# Bypass_FPGA_1V2.net
KiCad netlist of a schematic drawn in Altium Designer
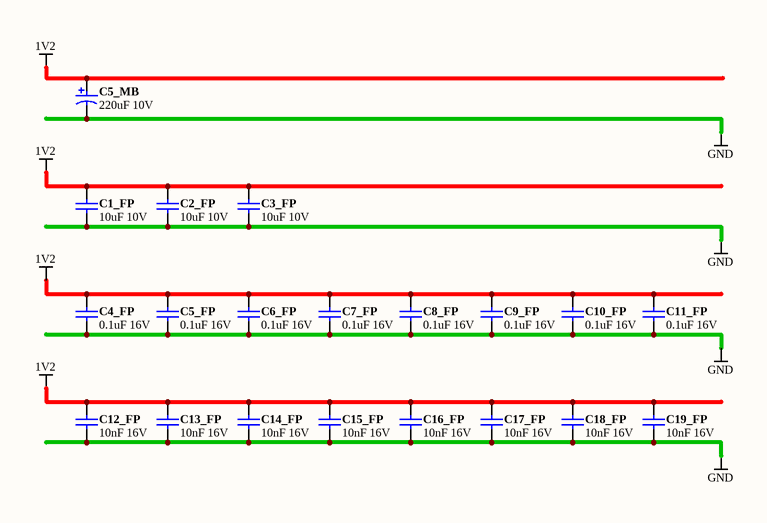
[diagram p0: Bypass_FPGA_1V2.SCHDOC]

(export (version "E")
  (design (tool "Eeschema 10.0.6"))
  (components
    (comp (ref "C1_FP")
      (value "10uF 10V")
      (footprint "CAPC2012-STAR")
      (description "Capacitor, Ceramic, 10uF 10% 10V 0805 (2012) X5R")
      (fields (field (name "TOLERANCE") "10 %"))
      (libsource (lib "AltiumDesignLibrary") (part "CAP-NP"))
    )
    (comp (ref "C2_FP")
      (value "10uF 10V")
      (footprint "CAPC2012-STAR")
      (description "Capacitor, Ceramic, 10uF 10% 10V 0805 (2012) X5R")
      (fields (field (name "TOLERANCE") "10 %"))
      (libsource (lib "AltiumDesignLibrary") (part "CAP-NP"))
    )
    (comp (ref "C3_FP")
      (value "10uF 10V")
      (footprint "CAPC2012-STAR")
      (description "Capacitor, Ceramic, 10uF 10% 10V 0805 (2012) X5R")
      (fields (field (name "TOLERANCE") "10 %"))
      (libsource (lib "AltiumDesignLibrary") (part "CAP-NP"))
    )
    (comp (ref "C4_FP")
      (value "0.1uF 16V")
      (footprint "CAPC1005-STAR")
      (description "Capacitor, Ceramic, 0.1uF 10% 16V 0402 (1005) X7R")
      (fields (field (name "TOLERANCE") "10 %"))
      (libsource (lib "AltiumDesignLibrary") (part "CAP-NP"))
    )
    (comp (ref "C5_FP")
      (value "0.1uF 16V")
      (footprint "CAPC1005-STAR")
      (description "Capacitor, Ceramic, 0.1uF 10% 16V 0402 (1005) X7R")
      (fields (field (name "TOLERANCE") "10 %"))
      (libsource (lib "AltiumDesignLibrary") (part "CAP-NP"))
    )
    (comp (ref "C5_MB")
      (value "220uF 10V")
      (footprint "CAPC7343-STAR")
      (description "Capacitor, Tantalum, 220uF 10% 10V MCCT-D (7343-31)")
      (fields (field (name "TOLERANCE") "10 %"))
      (libsource (lib "AltiumDesignLibrary") (part "CAP-P"))
    )
    (comp (ref "C6_FP")
      (value "0.1uF 16V")
      (footprint "CAPC1005-STAR")
      (description "Capacitor, Ceramic, 0.1uF 10% 16V 0402 (1005) X7R")
      (fields (field (name "TOLERANCE") "10 %"))
      (libsource (lib "AltiumDesignLibrary") (part "CAP-NP"))
    )
    (comp (ref "C7_FP")
      (value "0.1uF 16V")
      (footprint "CAPC1005-STAR")
      (description "Capacitor, Ceramic, 0.1uF 10% 16V 0402 (1005) X7R")
      (fields (field (name "TOLERANCE") "10 %"))
      (libsource (lib "AltiumDesignLibrary") (part "CAP-NP"))
    )
    (comp (ref "C8_FP")
      (value "0.1uF 16V")
      (footprint "CAPC1005-STAR")
      (description "Capacitor, Ceramic, 0.1uF 10% 16V 0402 (1005) X7R")
      (fields (field (name "TOLERANCE") "10 %"))
      (libsource (lib "AltiumDesignLibrary") (part "CAP-NP"))
    )
    (comp (ref "C9_FP")
      (value "0.1uF 16V")
      (footprint "CAPC1005-STAR")
      (description "Capacitor, Ceramic, 0.1uF 10% 16V 0402 (1005) X7R")
      (fields (field (name "TOLERANCE") "10 %"))
      (libsource (lib "AltiumDesignLibrary") (part "CAP-NP"))
    )
    (comp (ref "C10_FP")
      (value "0.1uF 16V")
      (footprint "CAPC1005-STAR")
      (description "Capacitor, Ceramic, 0.1uF 10% 16V 0402 (1005) X7R")
      (fields (field (name "TOLERANCE") "10 %"))
      (libsource (lib "AltiumDesignLibrary") (part "CAP-NP"))
    )
    (comp (ref "C11_FP")
      (value "0.1uF 16V")
      (footprint "CAPC1005-STAR")
      (description "Capacitor, Ceramic, 0.1uF 10% 16V 0402 (1005) X7R")
      (fields (field (name "TOLERANCE") "10 %"))
      (libsource (lib "AltiumDesignLibrary") (part "CAP-NP"))
    )
    (comp (ref "C12_FP")
      (value "10nF 16V")
      (footprint "CAPC1005-STAR")
      (description "Capacitor, Ceramic, 10nF 10% 16V 0402 (1005) X7R")
      (fields (field (name "TOLERANCE") "10 %"))
      (libsource (lib "AltiumDesignLibrary") (part "CAP-NP"))
    )
    (comp (ref "C13_FP")
      (value "10nF 16V")
      (footprint "CAPC1005-STAR")
      (description "Capacitor, Ceramic, 10nF 10% 16V 0402 (1005) X7R")
      (fields (field (name "TOLERANCE") "10 %"))
      (libsource (lib "AltiumDesignLibrary") (part "CAP-NP"))
    )
    (comp (ref "C14_FP")
      (value "10nF 16V")
      (footprint "CAPC1005-STAR")
      (description "Capacitor, Ceramic, 10nF 10% 16V 0402 (1005) X7R")
      (fields (field (name "TOLERANCE") "10 %"))
      (libsource (lib "AltiumDesignLibrary") (part "CAP-NP"))
    )
    (comp (ref "C15_FP")
      (value "10nF 16V")
      (footprint "CAPC1005-STAR")
      (description "Capacitor, Ceramic, 10nF 10% 16V 0402 (1005) X7R")
      (fields (field (name "TOLERANCE") "10 %"))
      (libsource (lib "AltiumDesignLibrary") (part "CAP-NP"))
    )
    (comp (ref "C16_FP")
      (value "10nF 16V")
      (footprint "CAPC1005-STAR")
      (description "Capacitor, Ceramic, 10nF 10% 16V 0402 (1005) X7R")
      (fields (field (name "TOLERANCE") "10 %"))
      (libsource (lib "AltiumDesignLibrary") (part "CAP-NP"))
    )
    (comp (ref "C17_FP")
      (value "10nF 16V")
      (footprint "CAPC1005-STAR")
      (description "Capacitor, Ceramic, 10nF 10% 16V 0402 (1005) X7R")
      (fields (field (name "TOLERANCE") "10 %"))
      (libsource (lib "AltiumDesignLibrary") (part "CAP-NP"))
    )
    (comp (ref "C18_FP")
      (value "10nF 16V")
      (footprint "CAPC1005-STAR")
      (description "Capacitor, Ceramic, 10nF 10% 16V 0402 (1005) X7R")
      (fields (field (name "TOLERANCE") "10 %"))
      (libsource (lib "AltiumDesignLibrary") (part "CAP-NP"))
    )
    (comp (ref "C19_FP")
      (value "10nF 16V")
      (footprint "CAPC1005-STAR")
      (description "Capacitor, Ceramic, 10nF 10% 16V 0402 (1005) X7R")
      (fields (field (name "TOLERANCE") "10 %"))
      (libsource (lib "AltiumDesignLibrary") (part "CAP-NP"))
    )
  )
  (nets
    (net (code "1") (name "1V2") (class "Default")
      (node (ref "C10_FP") (pin "1") (pinfunction "1_1") (pintype "passive"))
      (node (ref "C11_FP") (pin "1") (pinfunction "1_1") (pintype "passive"))
      (node (ref "C12_FP") (pin "1") (pinfunction "1_1") (pintype "passive"))
      (node (ref "C13_FP") (pin "1") (pinfunction "1_1") (pintype "passive"))
      (node (ref "C14_FP") (pin "1") (pinfunction "1_1") (pintype "passive"))
      (node (ref "C15_FP") (pin "1") (pinfunction "1_1") (pintype "passive"))
      (node (ref "C16_FP") (pin "1") (pinfunction "1_1") (pintype "passive"))
      (node (ref "C17_FP") (pin "1") (pinfunction "1_1") (pintype "passive"))
      (node (ref "C18_FP") (pin "1") (pinfunction "1_1") (pintype "passive"))
      (node (ref "C19_FP") (pin "1") (pinfunction "1_1") (pintype "passive"))
      (node (ref "C1_FP") (pin "1") (pinfunction "1_1") (pintype "passive"))
      (node (ref "C2_FP") (pin "1") (pinfunction "1_1") (pintype "passive"))
      (node (ref "C3_FP") (pin "1") (pinfunction "1_1") (pintype "passive"))
      (node (ref "C4_FP") (pin "1") (pinfunction "1_1") (pintype "passive"))
      (node (ref "C5_FP") (pin "1") (pinfunction "1_1") (pintype "passive"))
      (node (ref "C5_MB") (pin "1") (pinfunction "1_1") (pintype "passive"))
      (node (ref "C6_FP") (pin "1") (pinfunction "1_1") (pintype "passive"))
      (node (ref "C7_FP") (pin "1") (pinfunction "1_1") (pintype "passive"))
      (node (ref "C8_FP") (pin "1") (pinfunction "1_1") (pintype "passive"))
      (node (ref "C9_FP") (pin "1") (pinfunction "1_1") (pintype "passive"))
    )
    (net (code "2") (name "GND") (class "Default")
      (node (ref "C10_FP") (pin "2") (pinfunction "2_2") (pintype "passive"))
      (node (ref "C11_FP") (pin "2") (pinfunction "2_2") (pintype "passive"))
      (node (ref "C12_FP") (pin "2") (pinfunction "2_2") (pintype "passive"))
      (node (ref "C13_FP") (pin "2") (pinfunction "2_2") (pintype "passive"))
      (node (ref "C14_FP") (pin "2") (pinfunction "2_2") (pintype "passive"))
      (node (ref "C15_FP") (pin "2") (pinfunction "2_2") (pintype "passive"))
      (node (ref "C16_FP") (pin "2") (pinfunction "2_2") (pintype "passive"))
      (node (ref "C17_FP") (pin "2") (pinfunction "2_2") (pintype "passive"))
      (node (ref "C18_FP") (pin "2") (pinfunction "2_2") (pintype "passive"))
      (node (ref "C19_FP") (pin "2") (pinfunction "2_2") (pintype "passive"))
      (node (ref "C1_FP") (pin "2") (pinfunction "2_2") (pintype "passive"))
      (node (ref "C2_FP") (pin "2") (pinfunction "2_2") (pintype "passive"))
      (node (ref "C3_FP") (pin "2") (pinfunction "2_2") (pintype "passive"))
      (node (ref "C4_FP") (pin "2") (pinfunction "2_2") (pintype "passive"))
      (node (ref "C5_FP") (pin "2") (pinfunction "2_2") (pintype "passive"))
      (node (ref "C5_MB") (pin "2") (pinfunction "2_2") (pintype "passive"))
      (node (ref "C6_FP") (pin "2") (pinfunction "2_2") (pintype "passive"))
      (node (ref "C7_FP") (pin "2") (pinfunction "2_2") (pintype "passive"))
      (node (ref "C8_FP") (pin "2") (pinfunction "2_2") (pintype "passive"))
      (node (ref "C9_FP") (pin "2") (pinfunction "2_2") (pintype "passive"))
    )
  )
)
